# RS232_NPN_PNP_Negative_Mirrored.net
KiCad netlist of a schematic drawn in EAGLE
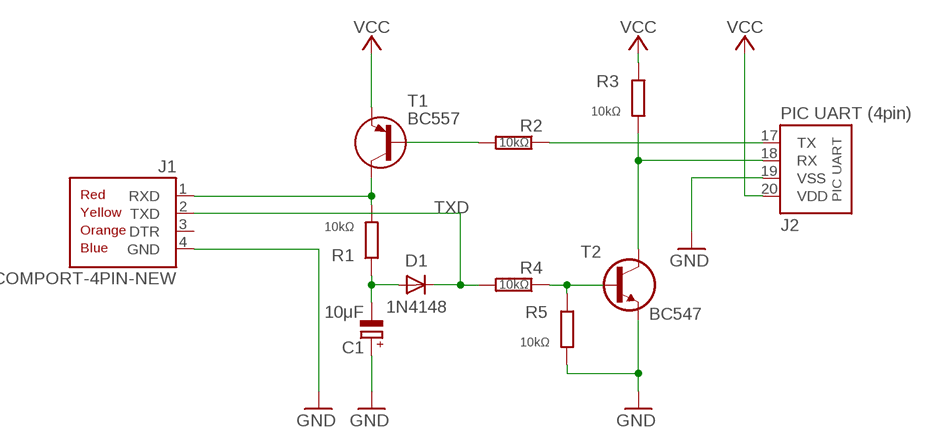
[diagram p0: schematic, sheet 1]

(export (version "E")
  (design (tool "Eeschema 10.0.6"))
  (components
    (comp (ref "C1")
      (value "10μF")
      (footprint "eagle-import:E2,5-3")
      (libsource (lib "eagle-import") (part "CPOLE2,5-3"))
    )
    (comp (ref "D1")
      (value "1N4148")
      (footprint "eagle-import:DO34-7")
      (libsource (lib "eagle-import") (part "1N414834-7"))
    )
    (comp (ref "J1")
      (value "COMPORT-4PIN-NEW")
      (footprint "eagle-import:RS232-4PIN-NEW")
      (libsource (lib "eagle-import") (part "COMPORT-4PIN-NEW"))
    )
    (comp (ref "J2")
      (value "PIC UART (4pin)")
      (footprint "eagle-import:PIC-UART-L")
      (libsource (lib "eagle-import") (part "PIC-UART-L"))
    )
    (comp (ref "R1")
      (value "10kΩ")
      (footprint "eagle-import:0202_7")
      (libsource (lib "eagle-import") (part "R0202/7"))
    )
    (comp (ref "R2")
      (value "10kΩ")
      (footprint "eagle-import:0202_10-V")
      (libsource (lib "eagle-import") (part "R0202/10-V"))
    )
    (comp (ref "R3")
      (value "10kΩ")
      (footprint "eagle-import:0202_7-V")
      (libsource (lib "eagle-import") (part "R0202/7-V"))
    )
    (comp (ref "R4")
      (value "10kΩ")
      (footprint "eagle-import:0202_7")
      (libsource (lib "eagle-import") (part "R0202/7"))
    )
    (comp (ref "R5")
      (value "10kΩ")
      (footprint "eagle-import:0202_7")
      (libsource (lib "eagle-import") (part "R0202/7"))
    )
    (comp (ref "T1")
      (value "BC557")
      (footprint "eagle-import:TO92-CBE")
      (libsource (lib "eagle-import") (part "BC557CBE"))
    )
    (comp (ref "T2")
      (value "BC547")
      (footprint "eagle-import:TO92-CBE")
      (libsource (lib "eagle-import") (part "BC547CBE"))
    )
  )
  (nets
    (net (code "1") (name "/TXD") (class "Default")
      (node (ref "D1") (pin "C") (pinfunction "C_C") (pintype "passive"))
      (node (ref "J1") (pin "2") (pinfunction "TXD_2") (pintype "passive"))
      (node (ref "R4") (pin "2") (pinfunction "2_2") (pintype "passive"))
    )
    (net (code "2") (name "GND") (class "Default")
      (node (ref "C1") (pin "+") (pinfunction "+_+") (pintype "passive"))
      (node (ref "J1") (pin "4") (pinfunction "GND_4") (pintype "passive"))
      (node (ref "J2") (pin "19") (pinfunction "VSS_19") (pintype "passive"))
      (node (ref "R5") (pin "2") (pinfunction "2_2") (pintype "passive"))
      (node (ref "T2") (pin "E") (pinfunction "E_E") (pintype "passive"))
    )
    (net (code "3") (name "Net-(C1-Pad-)") (class "Default")
      (node (ref "C1") (pin "-") (pinfunction "-_-") (pintype "passive"))
      (node (ref "D1") (pin "A") (pinfunction "A_A") (pintype "passive"))
      (node (ref "R1") (pin "1") (pinfunction "1_1") (pintype "passive"))
    )
    (net (code "4") (name "Net-(J1-RXD)") (class "Default")
      (node (ref "J1") (pin "1") (pinfunction "RXD_1") (pintype "passive"))
      (node (ref "R1") (pin "2") (pinfunction "2_2") (pintype "passive"))
      (node (ref "T1") (pin "C") (pinfunction "C_C") (pintype "passive"))
    )
    (net (code "5") (name "Net-(J2-RX)") (class "Default")
      (node (ref "J2") (pin "18") (pinfunction "RX_18") (pintype "passive"))
      (node (ref "R3") (pin "1") (pinfunction "1_1") (pintype "passive"))
      (node (ref "T2") (pin "C") (pinfunction "C_C") (pintype "passive"))
    )
    (net (code "6") (name "Net-(J2-TX)") (class "Default")
      (node (ref "J2") (pin "17") (pinfunction "TX_17") (pintype "passive"))
      (node (ref "R2") (pin "1") (pinfunction "1_1") (pintype "passive"))
    )
    (net (code "7") (name "Net-(R2-Pad2)") (class "Default")
      (node (ref "R2") (pin "2") (pinfunction "2_2") (pintype "passive"))
      (node (ref "T1") (pin "B") (pinfunction "B_B") (pintype "passive"))
    )
    (net (code "8") (name "Net-(R4-Pad1)") (class "Default")
      (node (ref "R4") (pin "1") (pinfunction "1_1") (pintype "passive"))
      (node (ref "R5") (pin "1") (pinfunction "1_1") (pintype "passive"))
      (node (ref "T2") (pin "B") (pinfunction "B_B") (pintype "passive"))
    )
    (net (code "9") (name "VCC") (class "Default")
      (node (ref "J2") (pin "20") (pinfunction "VDD_20") (pintype "passive"))
      (node (ref "R3") (pin "2") (pinfunction "2_2") (pintype "passive"))
      (node (ref "T1") (pin "E") (pinfunction "E_E") (pintype "passive"))
    )
    (net (code "10") (name "unconnected-(J1-DTR-Pad3)") (class "Default")
      (node (ref "J1") (pin "3") (pinfunction "DTR_3") (pintype "passive"))
    )
  )
)
